# PWM_v1_1.net
KiCad netlist of a schematic drawn in EAGLE
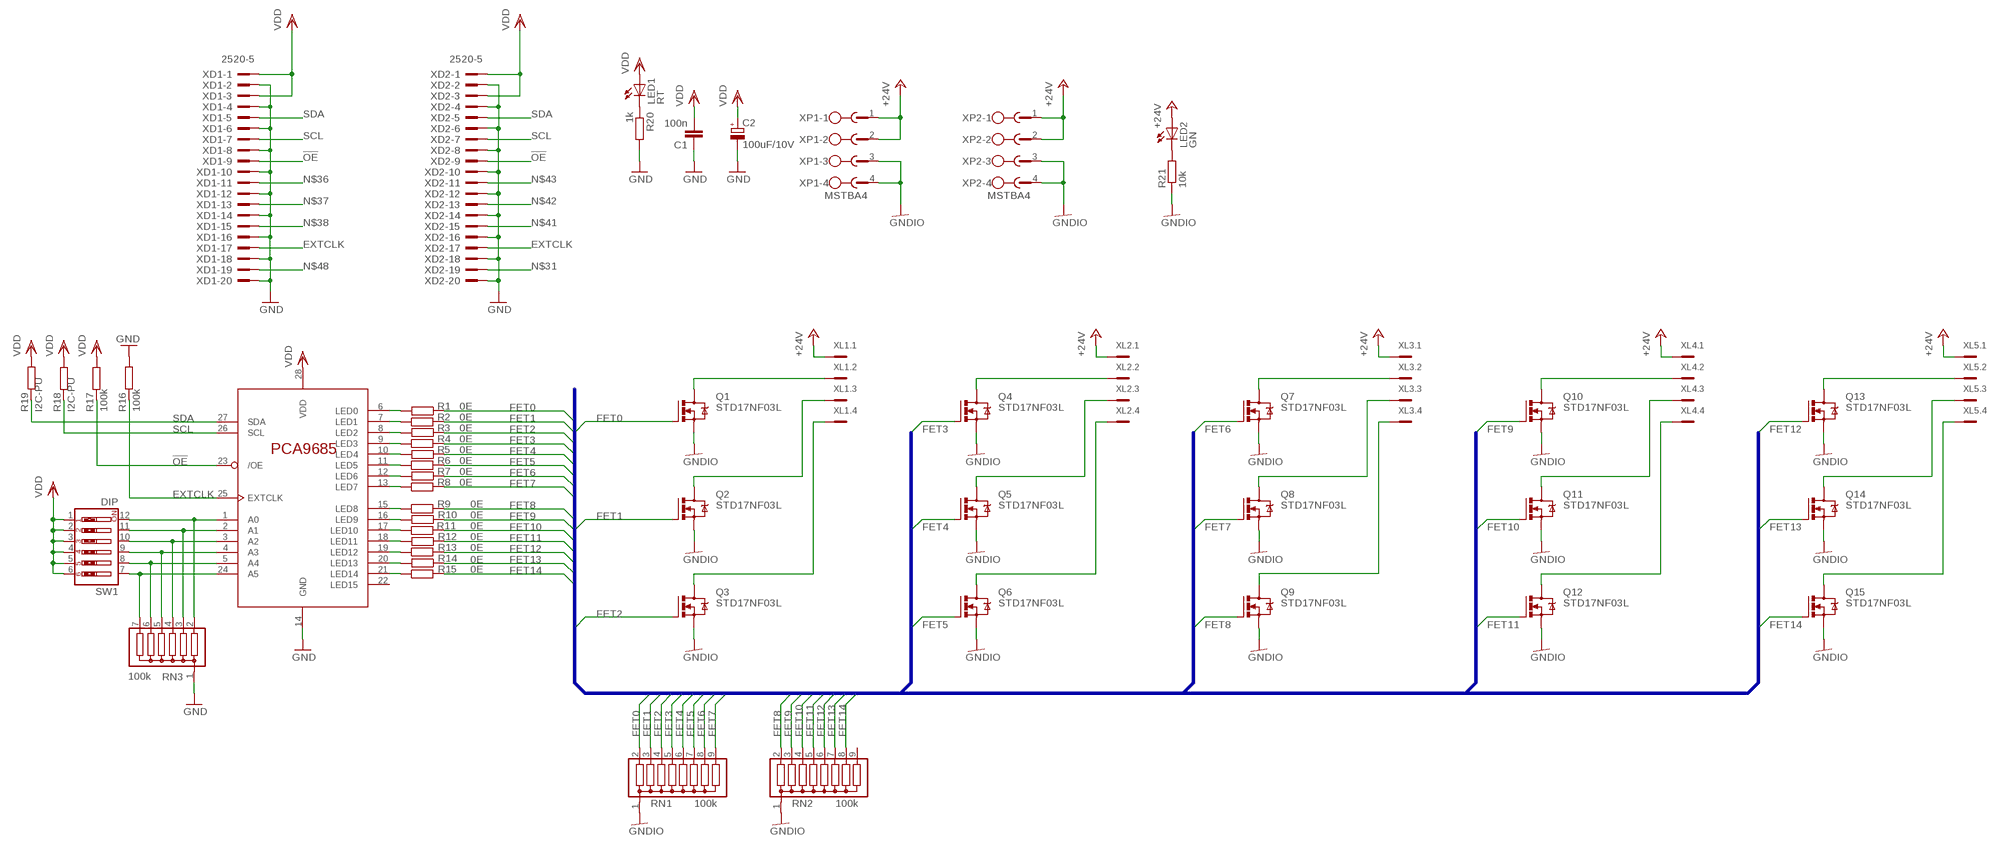
[diagram p0: schematic, sheet 1]

(export (version "E")
  (design (tool "Eeschema 10.0.6"))
  (components
    (comp (ref "C1")
      (value "100n")
      (footprint "eagle-import:C025_050-035X075")
      (libsource (lib "eagle-import") (part "C-EU025_050-035X075"))
    )
    (comp (ref "C2")
      (value "100uF/10V")
      (footprint "eagle-import:E5-10,5")
      (libsource (lib "eagle-import") (part "CPOL-EUE5-10.5"))
    )
    (comp (ref "IC1")
      (value "PCA9685")
      (footprint "eagle-import:DIL28-6")
      (libsource (lib "eagle-import") (part "PCA9685"))
    )
    (comp (ref "LED1")
      (value "RT")
      (footprint "eagle-import:LED3MM")
      (libsource (lib "eagle-import") (part "LED3MM"))
    )
    (comp (ref "LED2")
      (value "GN")
      (footprint "eagle-import:LED3MM")
      (libsource (lib "eagle-import") (part "LED3MM"))
    )
    (comp (ref "Q1")
      (value "STD17NF03L")
      (footprint "eagle-import:TO251AA-V")
      (libsource (lib "eagle-import") (part "STD17NF03L"))
    )
    (comp (ref "Q2")
      (value "STD17NF03L")
      (footprint "eagle-import:TO251AA-V")
      (libsource (lib "eagle-import") (part "STD17NF03L"))
    )
    (comp (ref "Q3")
      (value "STD17NF03L")
      (footprint "eagle-import:TO251AA-V")
      (libsource (lib "eagle-import") (part "STD17NF03L"))
    )
    (comp (ref "Q4")
      (value "STD17NF03L")
      (footprint "eagle-import:TO251AA-V")
      (libsource (lib "eagle-import") (part "STD17NF03L"))
    )
    (comp (ref "Q5")
      (value "STD17NF03L")
      (footprint "eagle-import:TO251AA-V")
      (libsource (lib "eagle-import") (part "STD17NF03L"))
    )
    (comp (ref "Q6")
      (value "STD17NF03L")
      (footprint "eagle-import:TO251AA-V")
      (libsource (lib "eagle-import") (part "STD17NF03L"))
    )
    (comp (ref "Q7")
      (value "STD17NF03L")
      (footprint "eagle-import:TO251AA-V")
      (libsource (lib "eagle-import") (part "STD17NF03L"))
    )
    (comp (ref "Q8")
      (value "STD17NF03L")
      (footprint "eagle-import:TO251AA-V")
      (libsource (lib "eagle-import") (part "STD17NF03L"))
    )
    (comp (ref "Q9")
      (value "STD17NF03L")
      (footprint "eagle-import:TO251AA-V")
      (libsource (lib "eagle-import") (part "STD17NF03L"))
    )
    (comp (ref "Q10")
      (value "STD17NF03L")
      (footprint "eagle-import:TO251AA-V")
      (libsource (lib "eagle-import") (part "STD17NF03L"))
    )
    (comp (ref "Q11")
      (value "STD17NF03L")
      (footprint "eagle-import:TO251AA-V")
      (libsource (lib "eagle-import") (part "STD17NF03L"))
    )
    (comp (ref "Q12")
      (value "STD17NF03L")
      (footprint "eagle-import:TO251AA-V")
      (libsource (lib "eagle-import") (part "STD17NF03L"))
    )
    (comp (ref "Q13")
      (value "STD17NF03L")
      (footprint "eagle-import:TO251AA-V")
      (libsource (lib "eagle-import") (part "STD17NF03L"))
    )
    (comp (ref "Q14")
      (value "STD17NF03L")
      (footprint "eagle-import:TO251AA-V")
      (libsource (lib "eagle-import") (part "STD17NF03L"))
    )
    (comp (ref "Q15")
      (value "STD17NF03L")
      (footprint "eagle-import:TO251AA-V")
      (libsource (lib "eagle-import") (part "STD17NF03L"))
    )
    (comp (ref "R1")
      (value "0E")
      (footprint "eagle-import:0207_2V")
      (libsource (lib "eagle-import") (part "R-EU_0207/2V"))
    )
    (comp (ref "R2")
      (value "0E")
      (footprint "eagle-import:0207_2V")
      (libsource (lib "eagle-import") (part "R-EU_0207/2V"))
    )
    (comp (ref "R3")
      (value "0E")
      (footprint "eagle-import:0207_2V")
      (libsource (lib "eagle-import") (part "R-EU_0207/2V"))
    )
    (comp (ref "R4")
      (value "0E")
      (footprint "eagle-import:0207_2V")
      (libsource (lib "eagle-import") (part "R-EU_0207/2V"))
    )
    (comp (ref "R5")
      (value "0E")
      (footprint "eagle-import:0207_2V")
      (libsource (lib "eagle-import") (part "R-EU_0207/2V"))
    )
    (comp (ref "R6")
      (value "0E")
      (footprint "eagle-import:0207_2V")
      (libsource (lib "eagle-import") (part "R-EU_0207/2V"))
    )
    (comp (ref "R7")
      (value "0E")
      (footprint "eagle-import:0207_2V")
      (libsource (lib "eagle-import") (part "R-EU_0207/2V"))
    )
    (comp (ref "R8")
      (value "0E")
      (footprint "eagle-import:0207_2V")
      (libsource (lib "eagle-import") (part "R-EU_0207/2V"))
    )
    (comp (ref "R9")
      (value "0E")
      (footprint "eagle-import:0207_2V")
      (libsource (lib "eagle-import") (part "R-EU_0207/2V"))
    )
    (comp (ref "R10")
      (value "0E")
      (footprint "eagle-import:0207_2V")
      (libsource (lib "eagle-import") (part "R-EU_0207/2V"))
    )
    (comp (ref "R11")
      (value "0E")
      (footprint "eagle-import:0207_2V")
      (libsource (lib "eagle-import") (part "R-EU_0207/2V"))
    )
    (comp (ref "R12")
      (value "0E")
      (footprint "eagle-import:0207_2V")
      (libsource (lib "eagle-import") (part "R-EU_0207/2V"))
    )
    (comp (ref "R13")
      (value "0E")
      (footprint "eagle-import:0207_2V")
      (libsource (lib "eagle-import") (part "R-EU_0207/2V"))
    )
    (comp (ref "R14")
      (value "0E")
      (footprint "eagle-import:0207_2V")
      (libsource (lib "eagle-import") (part "R-EU_0207/2V"))
    )
    (comp (ref "R15")
      (value "0E")
      (footprint "eagle-import:0207_2V")
      (libsource (lib "eagle-import") (part "R-EU_0207/2V"))
    )
    (comp (ref "R16")
      (value "100k")
      (footprint "eagle-import:0207_2V")
      (libsource (lib "eagle-import") (part "R-EU_0207/2V"))
    )
    (comp (ref "R17")
      (value "100k")
      (footprint "eagle-import:0207_2V")
      (libsource (lib "eagle-import") (part "R-EU_0207/2V"))
    )
    (comp (ref "R18")
      (value "I2C-PU")
      (footprint "eagle-import:0207_2V")
      (libsource (lib "eagle-import") (part "R-EU_0207/2V"))
    )
    (comp (ref "R19")
      (value "I2C-PU")
      (footprint "eagle-import:0207_2V")
      (libsource (lib "eagle-import") (part "R-EU_0207/2V"))
    )
    (comp (ref "R20")
      (value "1k")
      (footprint "eagle-import:0207_2V")
      (libsource (lib "eagle-import") (part "R-EU_0207/2V"))
    )
    (comp (ref "R21")
      (value "10k")
      (footprint "eagle-import:0207_2V")
      (libsource (lib "eagle-import") (part "R-EU_0207/2V"))
    )
    (comp (ref "RN1")
      (value "100k")
      (footprint "eagle-import:SIL9")
      (libsource (lib "eagle-import") (part "G08R"))
    )
    (comp (ref "RN2")
      (value "100k")
      (footprint "eagle-import:SIL9")
      (fields (field (name "OC_FARNELL") "unknown") (field (name "OC_NEWARK") "unknown"))
      (libsource (lib "eagle-import") (part "G08R"))
    )
    (comp (ref "RN3")
      (value "100k")
      (footprint "eagle-import:SIL7")
      (libsource (lib "eagle-import") (part "G06R"))
    )
    (comp (ref "SW1")
      (value "DIP")
      (footprint "eagle-import:EDG-06")
      (libsource (lib "eagle-import") (part "SW_DIP-6"))
    )
    (comp (ref "XD1")
      (value "2520-5")
      (footprint "eagle-import:PAK100_2500-5-20")
      (fields (field (name "MPN") "D2520-5002-AR"))
      (libsource (lib "eagle-import") (part "2520-5"))
    )
    (comp (ref "XD2")
      (value "2520-5")
      (footprint "eagle-import:PAK100_2500-5-20")
      (fields (field (name "MPN") "D2520-5002-AR"))
      (libsource (lib "eagle-import") (part "2520-5"))
    )
    (comp (ref "XL1")
      (value "MC4")
      (footprint "eagle-import:MC4")
      (libsource (lib "eagle-import") (part "MC4"))
    )
    (comp (ref "XL2")
      (value "MC4")
      (footprint "eagle-import:MC4")
      (libsource (lib "eagle-import") (part "MC4"))
    )
    (comp (ref "XL3")
      (value "MC4")
      (footprint "eagle-import:MC4")
      (libsource (lib "eagle-import") (part "MC4"))
    )
    (comp (ref "XL4")
      (value "MC4")
      (footprint "eagle-import:MC4")
      (libsource (lib "eagle-import") (part "MC4"))
    )
    (comp (ref "XL5")
      (value "MC4")
      (footprint "eagle-import:MC4")
      (libsource (lib "eagle-import") (part "MC4"))
    )
    (comp (ref "XP1")
      (value "MSTBA4")
      (footprint "eagle-import:MSTBA4")
      (fields (field (name "MF") "FARNELL") (field (name "MPN") "1757268"))
      (libsource (lib "eagle-import") (part "MSTBA4"))
    )
    (comp (ref "XP2")
      (value "MSTBA4")
      (footprint "eagle-import:MSTBA4")
      (fields (field (name "MF") "FARNELL") (field (name "MPN") "1757268"))
      (libsource (lib "eagle-import") (part "MSTBA4"))
    )
  )
  (nets
    (net (code "1") (name "+24V") (class "Default")
      (node (ref "LED2") (pin "A") (pinfunction "A_A") (pintype "passive"))
      (node (ref "XL1") (pin "1") (pinfunction "SK_1") (pintype "passive"))
      (node (ref "XL2") (pin "1") (pinfunction "SK_1") (pintype "passive"))
      (node (ref "XL3") (pin "1") (pinfunction "SK_1") (pintype "passive"))
      (node (ref "XL4") (pin "1") (pinfunction "SK_1") (pintype "passive"))
      (node (ref "XL5") (pin "1") (pinfunction "SK_1") (pintype "passive"))
      (node (ref "XP1") (pin "1") (pinfunction "1_1") (pintype "passive"))
      (node (ref "XP1") (pin "2") (pinfunction "1_2") (pintype "passive"))
      (node (ref "XP2") (pin "1") (pinfunction "1_1") (pintype "passive"))
      (node (ref "XP2") (pin "2") (pinfunction "1_2") (pintype "passive"))
    )
    (net (code "2") (name "/EXTCLK") (class "Default")
      (node (ref "IC1") (pin "25") (pinfunction "EXTCLK_25") (pintype "input"))
      (node (ref "R16") (pin "1") (pinfunction "1_1") (pintype "passive"))
      (node (ref "XD1") (pin "17") (pinfunction "KL_17") (pintype "passive"))
      (node (ref "XD2") (pin "17") (pinfunction "KL_17") (pintype "passive"))
    )
    (net (code "3") (name "/FET0") (class "Default")
      (node (ref "Q1") (pin "1") (pinfunction "G_1") (pintype "passive"))
      (node (ref "R1") (pin "1") (pinfunction "1_1") (pintype "passive"))
      (node (ref "RN1") (pin "9") (pinfunction "9_9") (pintype "passive"))
    )
    (net (code "4") (name "/FET1") (class "Default")
      (node (ref "Q2") (pin "1") (pinfunction "G_1") (pintype "passive"))
      (node (ref "R2") (pin "2") (pinfunction "2_2") (pintype "passive"))
      (node (ref "RN1") (pin "8") (pinfunction "8_8") (pintype "passive"))
    )
    (net (code "5") (name "/FET2") (class "Default")
      (node (ref "Q3") (pin "1") (pinfunction "G_1") (pintype "passive"))
      (node (ref "R3") (pin "1") (pinfunction "1_1") (pintype "passive"))
      (node (ref "RN1") (pin "7") (pinfunction "7_7") (pintype "passive"))
    )
    (net (code "6") (name "/FET3") (class "Default")
      (node (ref "Q4") (pin "1") (pinfunction "G_1") (pintype "passive"))
      (node (ref "R4") (pin "2") (pinfunction "2_2") (pintype "passive"))
      (node (ref "RN1") (pin "6") (pinfunction "6_6") (pintype "passive"))
    )
    (net (code "7") (name "/FET4") (class "Default")
      (node (ref "Q5") (pin "1") (pinfunction "G_1") (pintype "passive"))
      (node (ref "R5") (pin "1") (pinfunction "1_1") (pintype "passive"))
      (node (ref "RN1") (pin "5") (pinfunction "5_5") (pintype "passive"))
    )
    (net (code "8") (name "/FET5") (class "Default")
      (node (ref "Q6") (pin "1") (pinfunction "G_1") (pintype "passive"))
      (node (ref "R6") (pin "2") (pinfunction "2_2") (pintype "passive"))
      (node (ref "RN1") (pin "4") (pinfunction "4_4") (pintype "passive"))
    )
    (net (code "9") (name "/FET6") (class "Default")
      (node (ref "Q7") (pin "1") (pinfunction "G_1") (pintype "passive"))
      (node (ref "R7") (pin "1") (pinfunction "1_1") (pintype "passive"))
      (node (ref "RN1") (pin "3") (pinfunction "3_3") (pintype "passive"))
    )
    (net (code "10") (name "/FET7") (class "Default")
      (node (ref "Q8") (pin "1") (pinfunction "G_1") (pintype "passive"))
      (node (ref "R8") (pin "2") (pinfunction "2_2") (pintype "passive"))
      (node (ref "RN1") (pin "2") (pinfunction "2_2") (pintype "passive"))
    )
    (net (code "11") (name "/FET8") (class "Default")
      (node (ref "Q9") (pin "1") (pinfunction "G_1") (pintype "passive"))
      (node (ref "R9") (pin "2") (pinfunction "2_2") (pintype "passive"))
      (node (ref "RN2") (pin "2") (pinfunction "2_2") (pintype "passive"))
    )
    (net (code "12") (name "/FET9") (class "Default")
      (node (ref "Q10") (pin "1") (pinfunction "G_1") (pintype "passive"))
      (node (ref "R10") (pin "1") (pinfunction "1_1") (pintype "passive"))
      (node (ref "RN2") (pin "3") (pinfunction "3_3") (pintype "passive"))
    )
    (net (code "13") (name "/FET10") (class "Default")
      (node (ref "Q11") (pin "1") (pinfunction "G_1") (pintype "passive"))
      (node (ref "R11") (pin "2") (pinfunction "2_2") (pintype "passive"))
      (node (ref "RN2") (pin "4") (pinfunction "4_4") (pintype "passive"))
    )
    (net (code "14") (name "/FET11") (class "Default")
      (node (ref "Q12") (pin "1") (pinfunction "G_1") (pintype "passive"))
      (node (ref "R12") (pin "1") (pinfunction "1_1") (pintype "passive"))
      (node (ref "RN2") (pin "5") (pinfunction "5_5") (pintype "passive"))
    )
    (net (code "15") (name "/FET12") (class "Default")
      (node (ref "Q13") (pin "1") (pinfunction "G_1") (pintype "passive"))
      (node (ref "R13") (pin "2") (pinfunction "2_2") (pintype "passive"))
      (node (ref "RN2") (pin "6") (pinfunction "6_6") (pintype "passive"))
    )
    (net (code "16") (name "/FET13") (class "Default")
      (node (ref "Q14") (pin "1") (pinfunction "G_1") (pintype "passive"))
      (node (ref "R14") (pin "1") (pinfunction "1_1") (pintype "passive"))
      (node (ref "RN2") (pin "7") (pinfunction "7_7") (pintype "passive"))
    )
    (net (code "17") (name "/FET14") (class "Default")
      (node (ref "Q15") (pin "1") (pinfunction "G_1") (pintype "passive"))
      (node (ref "R15") (pin "2") (pinfunction "2_2") (pintype "passive"))
      (node (ref "RN2") (pin "8") (pinfunction "8_8") (pintype "passive"))
    )
    (net (code "18") (name "/N$31") (class "Default")
      (node (ref "XD2") (pin "19") (pinfunction "KL_19") (pintype "passive"))
    )
    (net (code "19") (name "/N$36") (class "Default")
      (node (ref "XD1") (pin "11") (pinfunction "KL_11") (pintype "passive"))
    )
    (net (code "20") (name "/N$37") (class "Default")
      (node (ref "XD1") (pin "13") (pinfunction "KL_13") (pintype "passive"))
    )
    (net (code "21") (name "/N$38") (class "Default")
      (node (ref "XD1") (pin "15") (pinfunction "KL_15") (pintype "passive"))
    )
    (net (code "22") (name "/N$41") (class "Default")
      (node (ref "XD2") (pin "15") (pinfunction "KL_15") (pintype "passive"))
    )
    (net (code "23") (name "/N$42") (class "Default")
      (node (ref "XD2") (pin "13") (pinfunction "KL_13") (pintype "passive"))
    )
    (net (code "24") (name "/N$43") (class "Default")
      (node (ref "XD2") (pin "11") (pinfunction "KL_11") (pintype "passive"))
    )
    (net (code "25") (name "/N$48") (class "Default")
      (node (ref "XD1") (pin "19") (pinfunction "KL_19") (pintype "passive"))
    )
    (net (code "26") (name "/SCL") (class "Default")
      (node (ref "IC1") (pin "26") (pinfunction "SCL_26") (pintype "bidirectional"))
      (node (ref "R18") (pin "2") (pinfunction "2_2") (pintype "passive"))
      (node (ref "XD1") (pin "7") (pinfunction "KL_7") (pintype "passive"))
      (node (ref "XD2") (pin "7") (pinfunction "KL_7") (pintype "passive"))
    )
    (net (code "27") (name "/SDA") (class "Default")
      (node (ref "IC1") (pin "27") (pinfunction "SDA_27") (pintype "bidirectional"))
      (node (ref "R19") (pin "1") (pinfunction "1_1") (pintype "passive"))
      (node (ref "XD1") (pin "5") (pinfunction "KL_5") (pintype "passive"))
      (node (ref "XD2") (pin "5") (pinfunction "KL_5") (pintype "passive"))
    )
    (net (code "28") (name "/~{OE}") (class "Default")
      (node (ref "IC1") (pin "23") (pinfunction "/OE_23") (pintype "bidirectional"))
      (node (ref "R17") (pin "2") (pinfunction "2_2") (pintype "passive"))
      (node (ref "XD1") (pin "9") (pinfunction "KL_9") (pintype "passive"))
      (node (ref "XD2") (pin "9") (pinfunction "KL_9") (pintype "passive"))
    )
    (net (code "29") (name "GND") (class "Default")
      (node (ref "C1") (pin "1") (pinfunction "1_1") (pintype "passive"))
      (node (ref "C2") (pin "-") (pinfunction "-_-") (pintype "passive"))
      (node (ref "IC1") (pin "14") (pinfunction "GND_14") (pintype "power_in"))
      (node (ref "R16") (pin "2") (pinfunction "2_2") (pintype "passive"))
      (node (ref "R20") (pin "2") (pinfunction "2_2") (pintype "passive"))
      (node (ref "RN3") (pin "1") (pinfunction "1_1") (pintype "passive"))
      (node (ref "XD1") (pin "10") (pinfunction "KL_10") (pintype "passive"))
      (node (ref "XD1") (pin "12") (pinfunction "KL_12") (pintype "passive"))
      (node (ref "XD1") (pin "14") (pinfunction "KL_14") (pintype "passive"))
      (node (ref "XD1") (pin "16") (pinfunction "KL_16") (pintype "passive"))
      (node (ref "XD1") (pin "18") (pinfunction "KL_18") (pintype "passive"))
      (node (ref "XD1") (pin "2") (pinfunction "KL_2") (pintype "passive"))
      (node (ref "XD1") (pin "20") (pinfunction "KL_20") (pintype "passive"))
      (node (ref "XD1") (pin "4") (pinfunction "KL_4") (pintype "passive"))
      (node (ref "XD1") (pin "6") (pinfunction "KL_6") (pintype "passive"))
      (node (ref "XD1") (pin "8") (pinfunction "KL_8") (pintype "passive"))
      (node (ref "XD2") (pin "10") (pinfunction "KL_10") (pintype "passive"))
      (node (ref "XD2") (pin "12") (pinfunction "KL_12") (pintype "passive"))
      (node (ref "XD2") (pin "14") (pinfunction "KL_14") (pintype "passive"))
      (node (ref "XD2") (pin "16") (pinfunction "KL_16") (pintype "passive"))
      (node (ref "XD2") (pin "18") (pinfunction "KL_18") (pintype "passive"))
      (node (ref "XD2") (pin "2") (pinfunction "KL_2") (pintype "passive"))
      (node (ref "XD2") (pin "20") (pinfunction "KL_20") (pintype "passive"))
      (node (ref "XD2") (pin "4") (pinfunction "KL_4") (pintype "passive"))
      (node (ref "XD2") (pin "6") (pinfunction "KL_6") (pintype "passive"))
      (node (ref "XD2") (pin "8") (pinfunction "KL_8") (pintype "passive"))
    )
    (net (code "30") (name "GNDIO") (class "Default")
      (node (ref "Q1") (pin "3") (pinfunction "S_3") (pintype "passive"))
      (node (ref "Q10") (pin "3") (pinfunction "S_3") (pintype "passive"))
      (node (ref "Q11") (pin "3") (pinfunction "S_3") (pintype "passive"))
      (node (ref "Q12") (pin "3") (pinfunction "S_3") (pintype "passive"))
      (node (ref "Q13") (pin "3") (pinfunction "S_3") (pintype "passive"))
      (node (ref "Q14") (pin "3") (pinfunction "S_3") (pintype "passive"))
      (node (ref "Q15") (pin "3") (pinfunction "S_3") (pintype "passive"))
      (node (ref "Q2") (pin "3") (pinfunction "S_3") (pintype "passive"))
      (node (ref "Q3") (pin "3") (pinfunction "S_3") (pintype "passive"))
      (node (ref "Q4") (pin "3") (pinfunction "S_3") (pintype "passive"))
      (node (ref "Q5") (pin "3") (pinfunction "S_3") (pintype "passive"))
      (node (ref "Q6") (pin "3") (pinfunction "S_3") (pintype "passive"))
      (node (ref "Q7") (pin "3") (pinfunction "S_3") (pintype "passive"))
      (node (ref "Q8") (pin "3") (pinfunction "S_3") (pintype "passive"))
      (node (ref "Q9") (pin "3") (pinfunction "S_3") (pintype "passive"))
      (node (ref "R21") (pin "1") (pinfunction "1_1") (pintype "passive"))
      (node (ref "RN1") (pin "1") (pinfunction "1_1") (pintype "passive"))
      (node (ref "RN2") (pin "1") (pinfunction "1_1") (pintype "passive"))
      (node (ref "XP1") (pin "3") (pinfunction "1_3") (pintype "passive"))
      (node (ref "XP1") (pin "4") (pinfunction "1_4") (pintype "passive"))
      (node (ref "XP2") (pin "3") (pinfunction "1_3") (pintype "passive"))
      (node (ref "XP2") (pin "4") (pinfunction "1_4") (pintype "passive"))
    )
    (net (code "31") (name "Net-(IC1-A0)") (class "Default")
      (node (ref "IC1") (pin "1") (pinfunction "A0_1") (pintype "bidirectional"))
      (node (ref "RN3") (pin "2") (pinfunction "2_2") (pintype "passive"))
      (node (ref "SW1") (pin "12") (pinfunction "12_12") (pintype "passive"))
    )
    (net (code "32") (name "Net-(IC1-A1)") (class "Default")
      (node (ref "IC1") (pin "2") (pinfunction "A1_2") (pintype "bidirectional"))
      (node (ref "RN3") (pin "3") (pinfunction "3_3") (pintype "passive"))
      (node (ref "SW1") (pin "11") (pinfunction "11_11") (pintype "passive"))
    )
    (net (code "33") (name "Net-(IC1-A2)") (class "Default")
      (node (ref "IC1") (pin "3") (pinfunction "A2_3") (pintype "bidirectional"))
      (node (ref "RN3") (pin "4") (pinfunction "4_4") (pintype "passive"))
      (node (ref "SW1") (pin "10") (pinfunction "10_10") (pintype "passive"))
    )
    (net (code "34") (name "Net-(IC1-A3)") (class "Default")
      (node (ref "IC1") (pin "4") (pinfunction "A3_4") (pintype "bidirectional"))
      (node (ref "RN3") (pin "5") (pinfunction "5_5") (pintype "passive"))
      (node (ref "SW1") (pin "9") (pinfunction "9_9") (pintype "passive"))
    )
    (net (code "35") (name "Net-(IC1-A4)") (class "Default")
      (node (ref "IC1") (pin "5") (pinfunction "A4_5") (pintype "bidirectional"))
      (node (ref "RN3") (pin "6") (pinfunction "6_6") (pintype "passive"))
      (node (ref "SW1") (pin "8") (pinfunction "8_8") (pintype "passive"))
    )
    (net (code "36") (name "Net-(IC1-A5)") (class "Default")
      (node (ref "IC1") (pin "24") (pinfunction "A5_24") (pintype "bidirectional"))
      (node (ref "RN3") (pin "7") (pinfunction "7_7") (pintype "passive"))
      (node (ref "SW1") (pin "7") (pinfunction "7_7") (pintype "passive"))
    )
    (net (code "37") (name "Net-(IC1-LED0)") (class "Default")
      (node (ref "IC1") (pin "6") (pinfunction "LED0_6") (pintype "bidirectional"))
      (node (ref "R1") (pin "2") (pinfunction "2_2") (pintype "passive"))
    )
    (net (code "38") (name "Net-(IC1-LED1)") (class "Default")
      (node (ref "IC1") (pin "7") (pinfunction "LED1_7") (pintype "bidirectional"))
      (node (ref "R2") (pin "1") (pinfunction "1_1") (pintype "passive"))
    )
    (net (code "39") (name "Net-(IC1-LED2)") (class "Default")
      (node (ref "IC1") (pin "8") (pinfunction "LED2_8") (pintype "bidirectional"))
      (node (ref "R3") (pin "2") (pinfunction "2_2") (pintype "passive"))
    )
    (net (code "40") (name "Net-(IC1-LED3)") (class "Default")
      (node (ref "IC1") (pin "9") (pinfunction "LED3_9") (pintype "bidirectional"))
      (node (ref "R4") (pin "1") (pinfunction "1_1") (pintype "passive"))
    )
    (net (code "41") (name "Net-(IC1-LED4)") (class "Default")
      (node (ref "IC1") (pin "10") (pinfunction "LED4_10") (pintype "bidirectional"))
      (node (ref "R5") (pin "2") (pinfunction "2_2") (pintype "passive"))
    )
    (net (code "42") (name "Net-(IC1-LED5)") (class "Default")
      (node (ref "IC1") (pin "11") (pinfunction "LED5_11") (pintype "bidirectional"))
      (node (ref "R6") (pin "1") (pinfunction "1_1") (pintype "passive"))
    )
    (net (code "43") (name "Net-(IC1-LED6)") (class "Default")
      (node (ref "IC1") (pin "12") (pinfunction "LED6_12") (pintype "bidirectional"))
      (node (ref "R7") (pin "2") (pinfunction "2_2") (pintype "passive"))
    )
    (net (code "44") (name "Net-(IC1-LED7)") (class "Default")
      (node (ref "IC1") (pin "13") (pinfunction "LED7_13") (pintype "bidirectional"))
      (node (ref "R8") (pin "1") (pinfunction "1_1") (pintype "passive"))
    )
    (net (code "45") (name "Net-(IC1-LED8)") (class "Default")
      (node (ref "IC1") (pin "15") (pinfunction "LED8_15") (pintype "bidirectional"))
      (node (ref "R9") (pin "1") (pinfunction "1_1") (pintype "passive"))
    )
    (net (code "46") (name "Net-(IC1-LED9)") (class "Default")
      (node (ref "IC1") (pin "16") (pinfunction "LED9_16") (pintype "bidirectional"))
      (node (ref "R10") (pin "2") (pinfunction "2_2") (pintype "passive"))
    )
    (net (code "47") (name "Net-(IC1-LED10)") (class "Default")
      (node (ref "IC1") (pin "17") (pinfunction "LED10_17") (pintype "bidirectional"))
      (node (ref "R11") (pin "1") (pinfunction "1_1") (pintype "passive"))
    )
    (net (code "48") (name "Net-(IC1-LED11)") (class "Default")
      (node (ref "IC1") (pin "18") (pinfunction "LED11_18") (pintype "bidirectional"))
      (node (ref "R12") (pin "2") (pinfunction "2_2") (pintype "passive"))
    )
    (net (code "49") (name "Net-(IC1-LED12)") (class "Default")
      (node (ref "IC1") (pin "19") (pinfunction "LED12_19") (pintype "bidirectional"))
      (node (ref "R13") (pin "1") (pinfunction "1_1") (pintype "passive"))
    )
    (net (code "50") (name "Net-(IC1-LED13)") (class "Default")
      (node (ref "IC1") (pin "20") (pinfunction "LED13_20") (pintype "bidirectional"))
      (node (ref "R14") (pin "2") (pinfunction "2_2") (pintype "passive"))
    )
    (net (code "51") (name "Net-(IC1-LED14)") (class "Default")
      (node (ref "IC1") (pin "21") (pinfunction "LED14_21") (pintype "bidirectional"))
      (node (ref "R15") (pin "1") (pinfunction "1_1") (pintype "passive"))
    )
    (net (code "52") (name "Net-(LED1-C)") (class "Default")
      (node (ref "LED1") (pin "K") (pinfunction "C_K") (pintype "passive"))
      (node (ref "R20") (pin "1") (pinfunction "1_1") (pintype "passive"))
    )
    (net (code "53") (name "Net-(LED2-C)") (class "Default")
      (node (ref "LED2") (pin "K") (pinfunction "C_K") (pintype "passive"))
      (node (ref "R21") (pin "2") (pinfunction "2_2") (pintype "passive"))
    )
    (net (code "54") (name "Net-(Q1-D)") (class "Default")
      (node (ref "Q1") (pin "2") (pinfunction "D_2") (pintype "passive"))
      (node (ref "XL1") (pin "2") (pinfunction "SK_2") (pintype "passive"))
    )
    (net (code "55") (name "Net-(Q2-D)") (class "Default")
      (node (ref "Q2") (pin "2") (pinfunction "D_2") (pintype "passive"))
      (node (ref "XL1") (pin "3") (pinfunction "SK_3") (pintype "passive"))
    )
    (net (code "56") (name "Net-(Q3-D)") (class "Default")
      (node (ref "Q3") (pin "2") (pinfunction "D_2") (pintype "passive"))
      (node (ref "XL1") (pin "4") (pinfunction "SK_4") (pintype "passive"))
    )
    (net (code "57") (name "Net-(Q4-D)") (class "Default")
      (node (ref "Q4") (pin "2") (pinfunction "D_2") (pintype "passive"))
      (node (ref "XL2") (pin "2") (pinfunction "SK_2") (pintype "passive"))
    )
    (net (code "58") (name "Net-(Q5-D)") (class "Default")
      (node (ref "Q5") (pin "2") (pinfunction "D_2") (pintype "passive"))
      (node (ref "XL2") (pin "3") (pinfunction "SK_3") (pintype "passive"))
    )
    (net (code "59") (name "Net-(Q6-D)") (class "Default")
      (node (ref "Q6") (pin "2") (pinfunction "D_2") (pintype "passive"))
      (node (ref "XL2") (pin "4") (pinfunction "SK_4") (pintype "passive"))
    )
    (net (code "60") (name "Net-(Q7-D)") (class "Default")
      (node (ref "Q7") (pin "2") (pinfunction "D_2") (pintype "passive"))
      (node (ref "XL3") (pin "2") (pinfunction "SK_2") (pintype "passive"))
    )
    (net (code "61") (name "Net-(Q8-D)") (class "Default")
      (node (ref "Q8") (pin "2") (pinfunction "D_2") (pintype "passive"))
      (node (ref "XL3") (pin "3") (pinfunction "SK_3") (pintype "passive"))
    )
    (net (code "62") (name "Net-(Q9-D)") (class "Default")
      (node (ref "Q9") (pin "2") (pinfunction "D_2") (pintype "passive"))
      (node (ref "XL3") (pin "4") (pinfunction "SK_4") (pintype "passive"))
    )
    (net (code "63") (name "Net-(Q10-D)") (class "Default")
      (node (ref "Q10") (pin "2") (pinfunction "D_2") (pintype "passive"))
      (node (ref "XL4") (pin "2") (pinfunction "SK_2") (pintype "passive"))
    )
    (net (code "64") (name "Net-(Q11-D)") (class "Default")
      (node (ref "Q11") (pin "2") (pinfunction "D_2") (pintype "passive"))
      (node (ref "XL4") (pin "3") (pinfunction "SK_3") (pintype "passive"))
    )
    (net (code "65") (name "Net-(Q12-D)") (class "Default")
      (node (ref "Q12") (pin "2") (pinfunction "D_2") (pintype "passive"))
      (node (ref "XL4") (pin "4") (pinfunction "SK_4") (pintype "passive"))
    )
    (net (code "66") (name "Net-(Q13-D)") (class "Default")
      (node (ref "Q13") (pin "2") (pinfunction "D_2") (pintype "passive"))
      (node (ref "XL5") (pin "2") (pinfunction "SK_2") (pintype "passive"))
    )
    (net (code "67") (name "Net-(Q14-D)") (class "Default")
      (node (ref "Q14") (pin "2") (pinfunction "D_2") (pintype "passive"))
      (node (ref "XL5") (pin "3") (pinfunction "SK_3") (pintype "passive"))
    )
    (net (code "68") (name "Net-(Q15-D)") (class "Default")
      (node (ref "Q15") (pin "2") (pinfunction "D_2") (pintype "passive"))
      (node (ref "XL5") (pin "4") (pinfunction "SK_4") (pintype "passive"))
    )
    (net (code "69") (name "VDD") (class "Default")
      (node (ref "C1") (pin "2") (pinfunction "2_2") (pintype "passive"))
      (node (ref "C2") (pin "+") (pinfunction "+_+") (pintype "passive"))
      (node (ref "IC1") (pin "28") (pinfunction "VDD_28") (pintype "power_in"))
      (node (ref "LED1") (pin "A") (pinfunction "A_A") (pintype "passive"))
      (node (ref "R17") (pin "1") (pinfunction "1_1") (pintype "passive"))
      (node (ref "R18") (pin "1") (pinfunction "1_1") (pintype "passive"))
      (node (ref "R19") (pin "2") (pinfunction "2_2") (pintype "passive"))
      (node (ref "SW1") (pin "1") (pinfunction "1_1") (pintype "passive"))
      (node (ref "SW1") (pin "2") (pinfunction "2_2") (pintype "passive"))
      (node (ref "SW1") (pin "3") (pinfunction "3_3") (pintype "passive"))
      (node (ref "SW1") (pin "4") (pinfunction "4_4") (pintype "passive"))
      (node (ref "SW1") (pin "5") (pinfunction "5_5") (pintype "passive"))
      (node (ref "SW1") (pin "6") (pinfunction "6_6") (pintype "passive"))
      (node (ref "XD1") (pin "1") (pinfunction "KL_1") (pintype "passive"))
      (node (ref "XD1") (pin "3") (pinfunction "KL_3") (pintype "passive"))
      (node (ref "XD2") (pin "1") (pinfunction "KL_1") (pintype "passive"))
      (node (ref "XD2") (pin "3") (pinfunction "KL_3") (pintype "passive"))
    )
    (net (code "70") (name "unconnected-(IC1-LED15-Pad22)") (class "Default")
      (node (ref "IC1") (pin "22") (pinfunction "LED15_22") (pintype "bidirectional"))
    )
    (net (code "71") (name "unconnected-(RN2-Pad9)") (class "Default")
      (node (ref "RN2") (pin "9") (pinfunction "9_9") (pintype "passive"))
    )
  )
)
